# ble-usb-v1_0.net
KiCad netlist of a schematic drawn in EAGLE
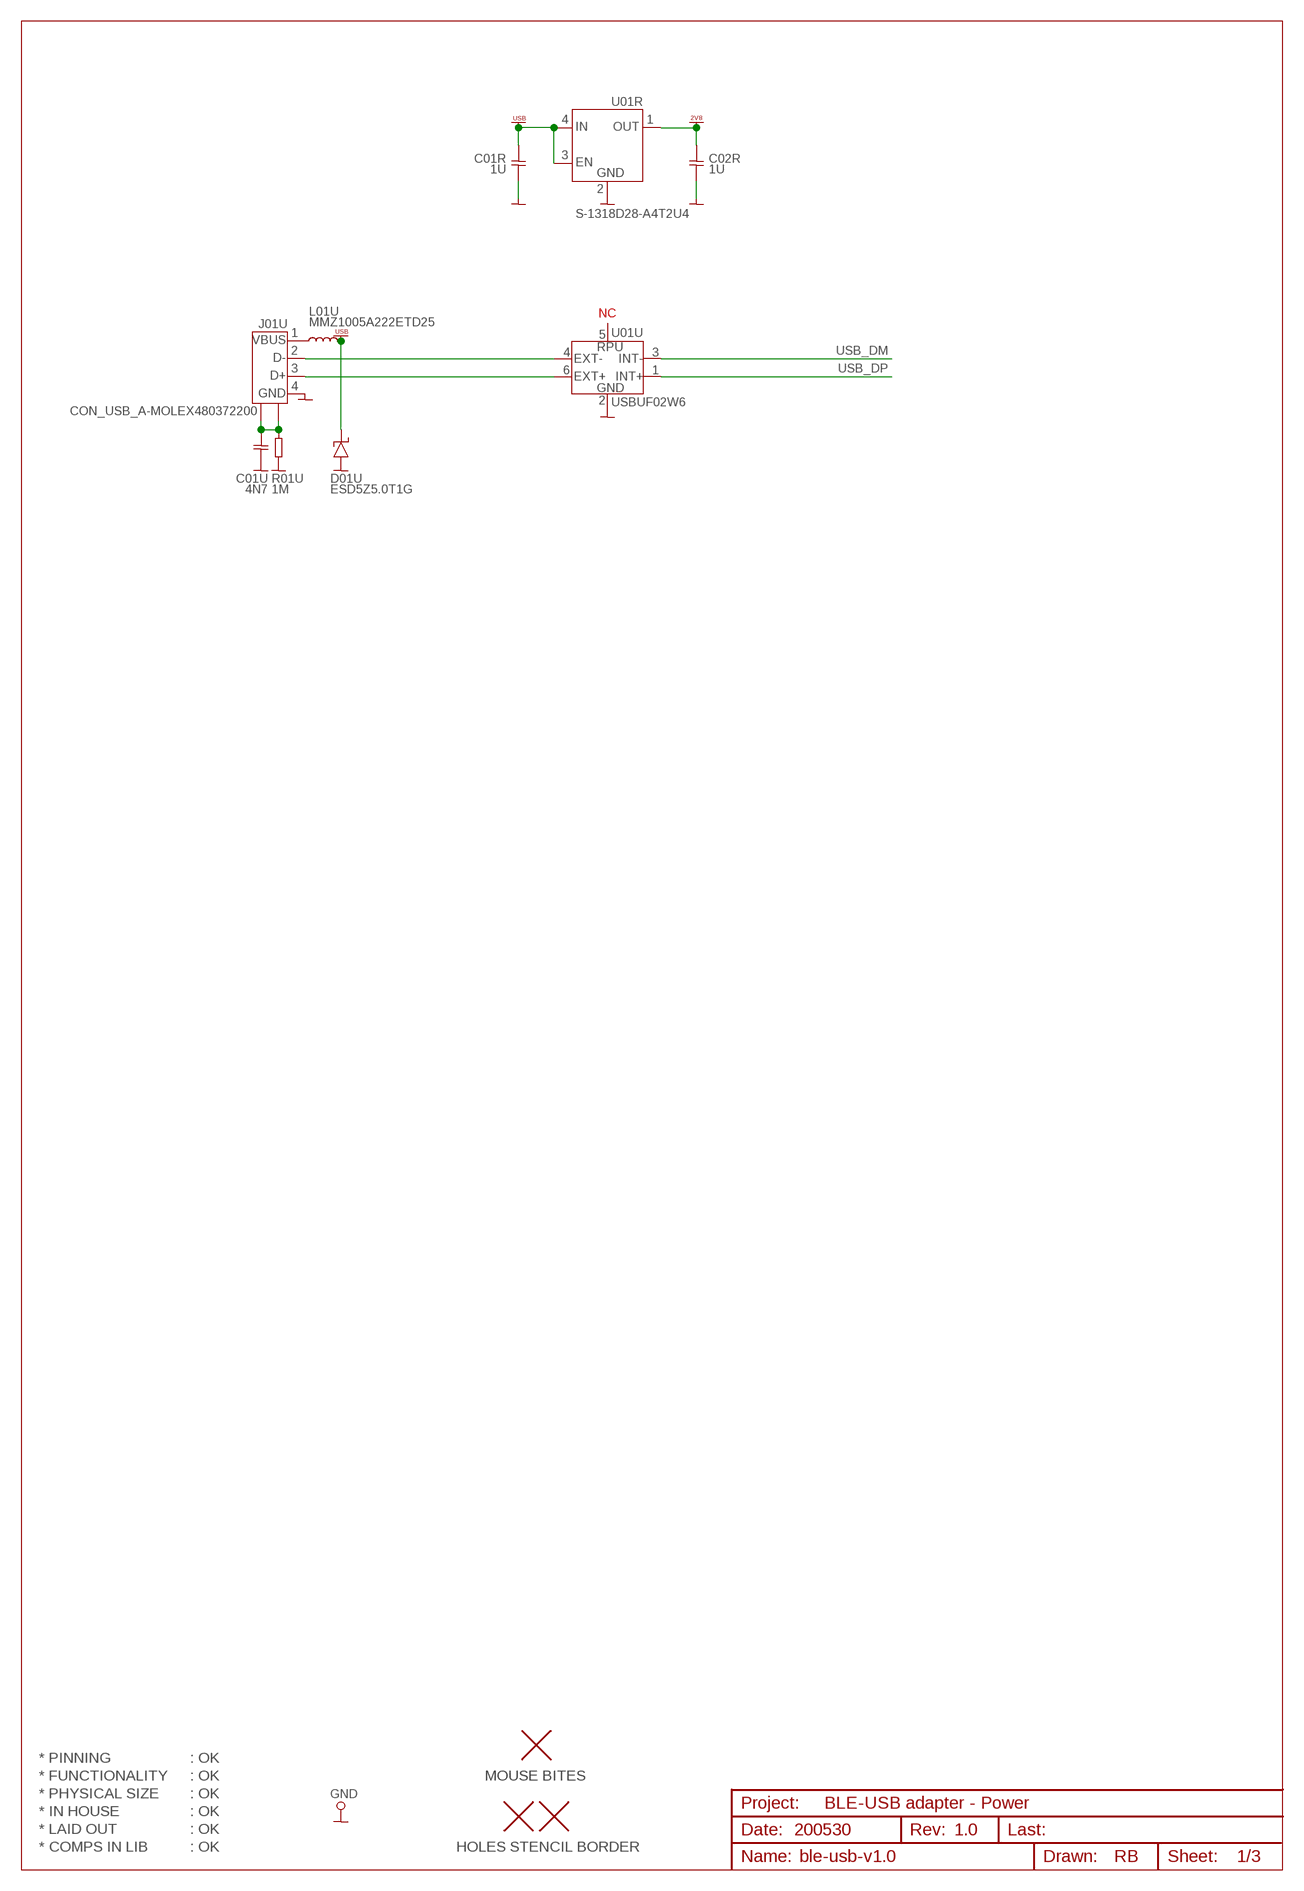
[diagram p0: schematic, sheet 1]
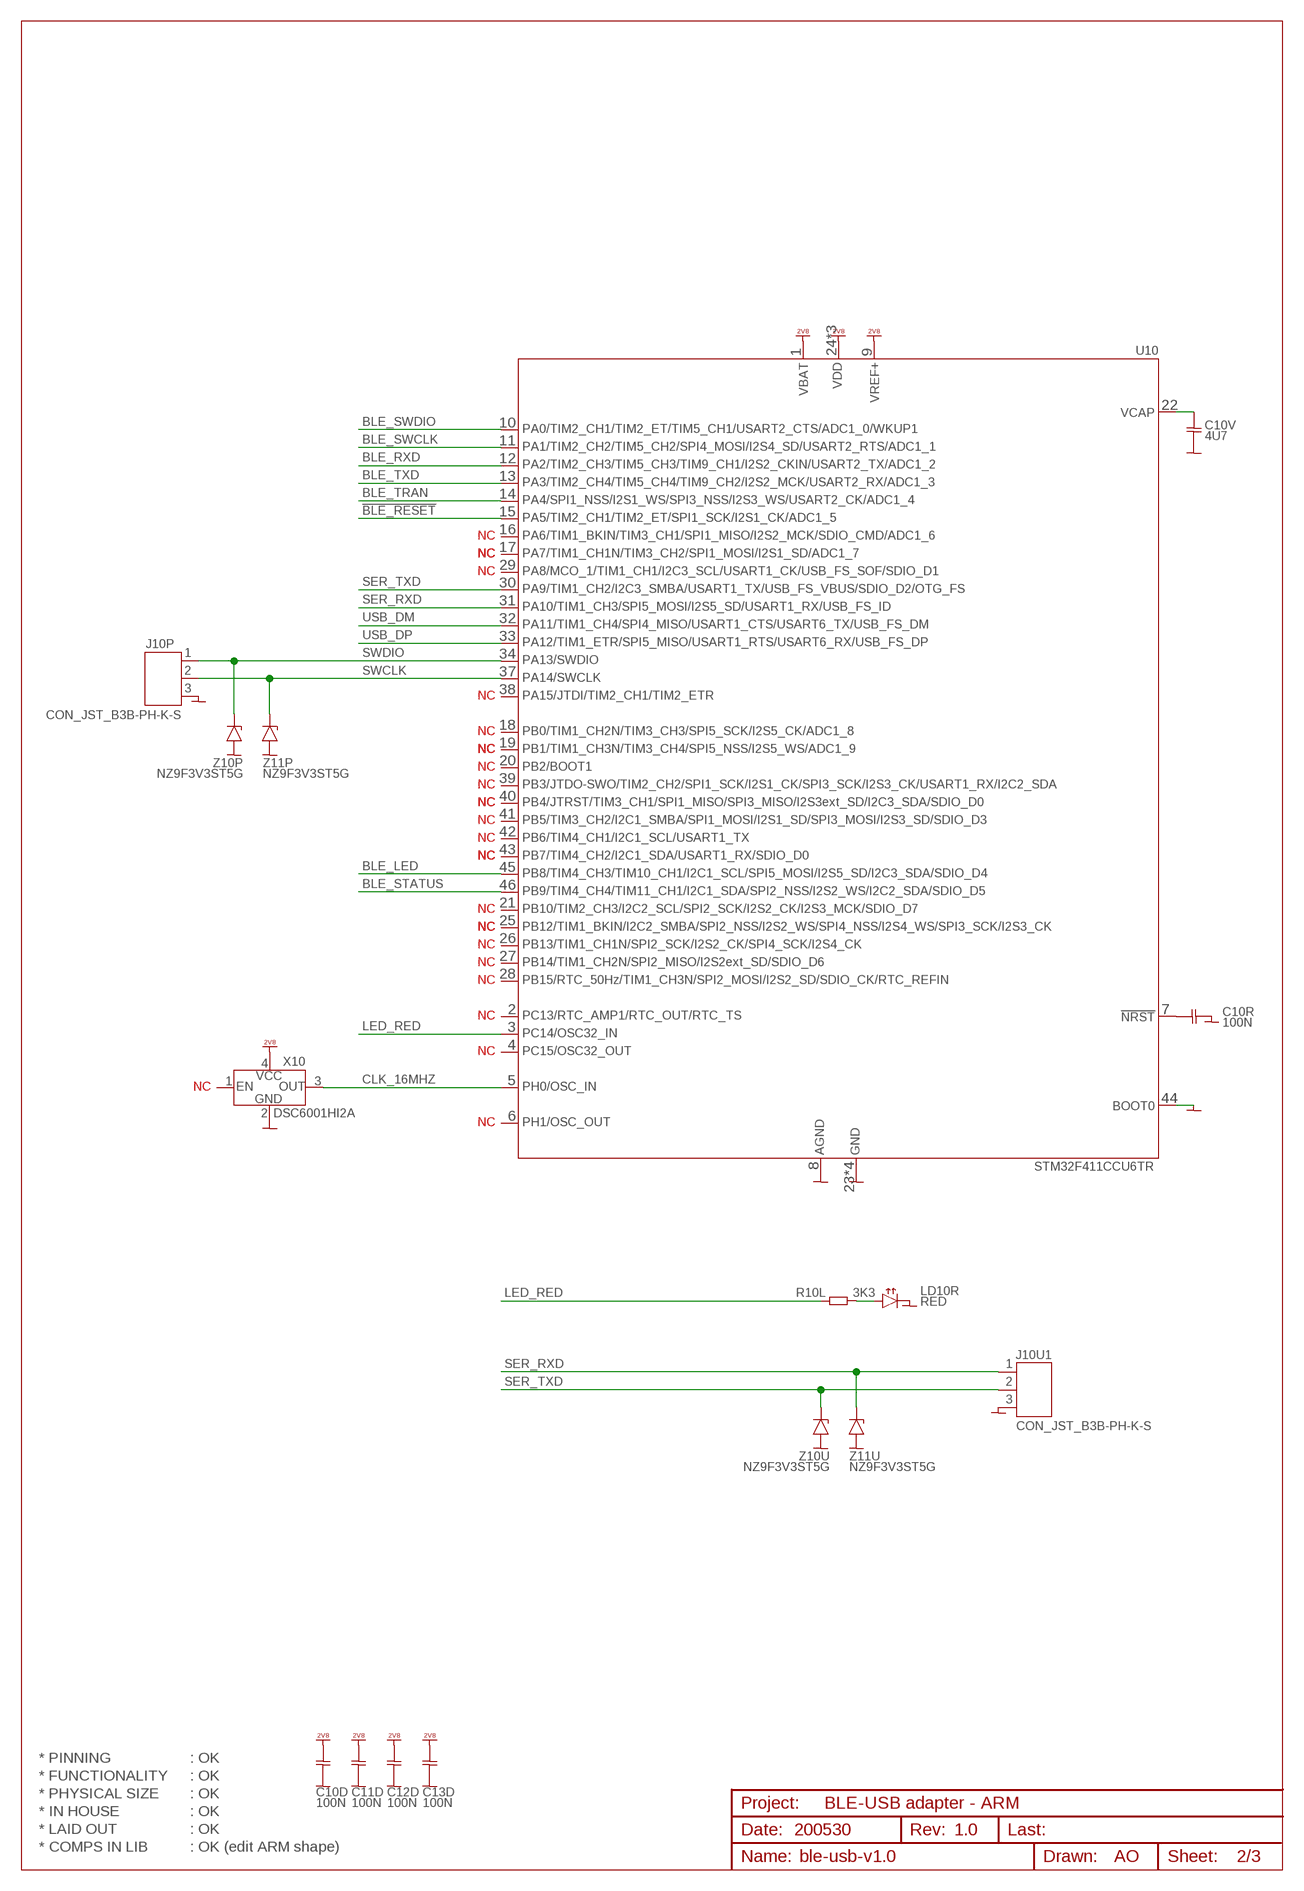
[diagram p1: schematic, sheet 2]
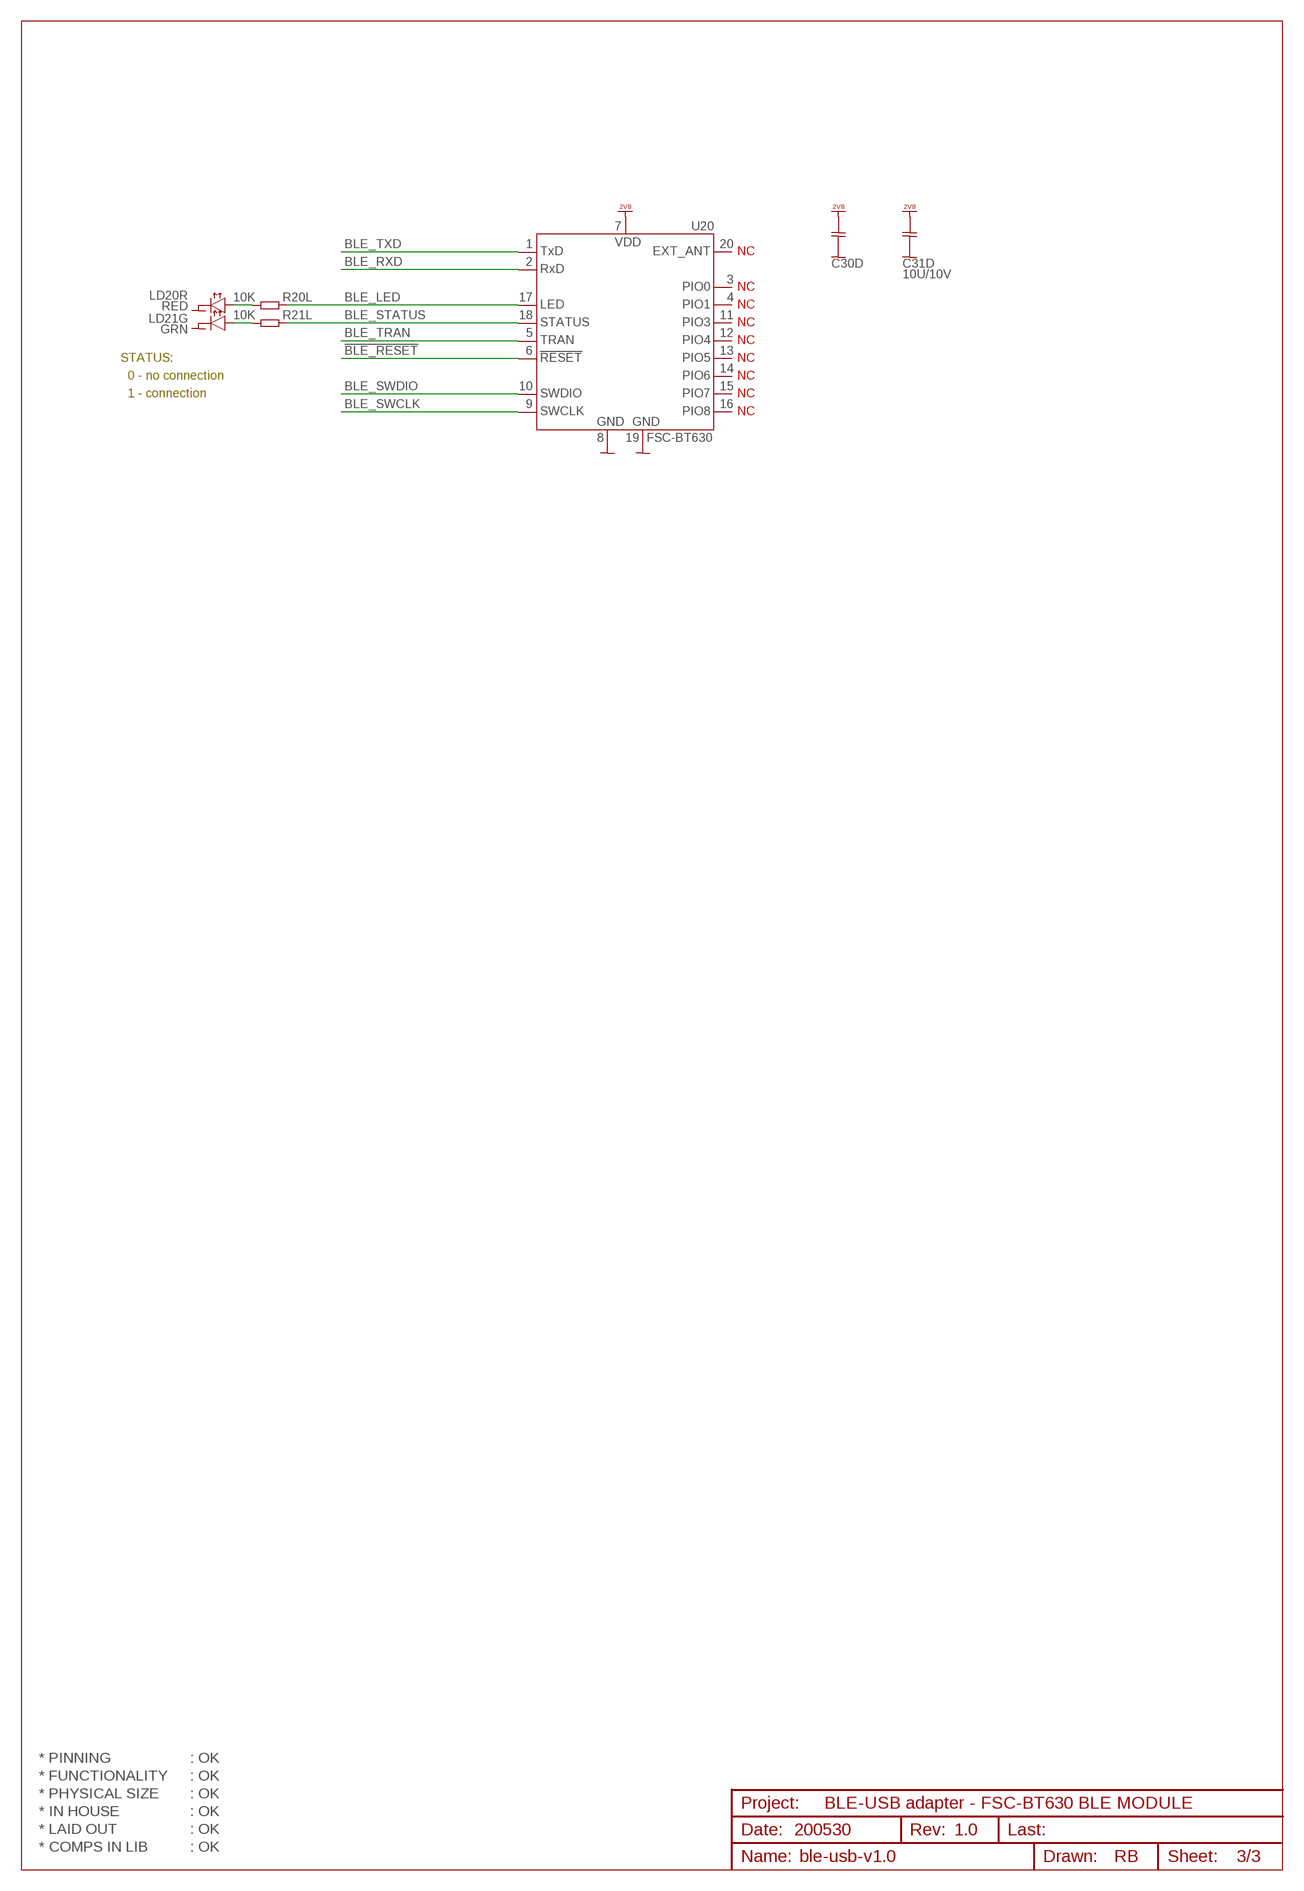
[diagram p2: schematic, sheet 3]

(export (version "E")
  (design (tool "Eeschema 10.0.6"))
  (components
    (comp (ref "C01R")
      (value "1U")
      (footprint "eagle-import:CAP0402")
      (libsource (lib "eagle-import") (part "CAP0402"))
    )
    (comp (ref "C01U")
      (value "4N7")
      (footprint "eagle-import:CAP0402")
      (libsource (lib "eagle-import") (part "CAP0402"))
    )
    (comp (ref "C02R")
      (value "1U")
      (footprint "eagle-import:CAP0402")
      (libsource (lib "eagle-import") (part "CAP0402"))
    )
    (comp (ref "D01U")
      (value "ESD5Z5.0T1G")
      (footprint "eagle-import:DIODE_SOD523")
      (libsource (lib "eagle-import") (part "DIODE_TVS_SOD523"))
    )
    (comp (ref "GND")
      (value "PIN_TEST_0.6MM")
      (footprint "eagle-import:HOLE_PTH_0.6MM")
      (libsource (lib "eagle-import") (part "PIN_TEST_0.6MM"))
    )
    (comp (ref "H1")
      (value "HOLE_NPTH_3.0MM-STENCILBORDER")
      (footprint "eagle-import:HOLE_NPTH_3,0MM-STECILBORDER")
      (libsource (lib "eagle-import") (part "HOLE_NPTH_3.0MM-STENCILBORDER"))
    )
    (comp (ref "H2")
      (value "HOLE_NPTH_3.0MM-STENCILBORDER")
      (footprint "eagle-import:HOLE_NPTH_3,0MM-STECILBORDER")
      (libsource (lib "eagle-import") (part "HOLE_NPTH_3.0MM-STENCILBORDER"))
    )
    (comp (ref "H10")
      (value "HOLE_MOUSEBITES")
      (footprint "eagle-import:HOLE_NPTH_0.5MM")
      (libsource (lib "eagle-import") (part "HOLE_MOUSEBITES"))
    )
    (comp (ref "J01U")
      (value "CON_USB_A-MOLEX480372200")
      (footprint "eagle-import:CON_USB_A-MOLEX480372200")
      (libsource (lib "eagle-import") (part "CON_USB_A-MOLEX480372200"))
    )
    (comp (ref "L01U")
      (value "MMZ1005A222ETD25")
      (footprint "eagle-import:L_0402")
      (libsource (lib "eagle-import") (part "L_0402"))
    )
    (comp (ref "R01U")
      (value "1M")
      (footprint "eagle-import:RES0402")
      (libsource (lib "eagle-import") (part "RES0402"))
    )
    (comp (ref "U01R")
      (value "S-1318D28-A4T2U4")
      (footprint "eagle-import:HSNT-4-B")
      (libsource (lib "eagle-import") (part "S-1318D28-A4T2U4"))
    )
    (comp (ref "U01U")
      (value "USBUF02W6")
      (footprint "eagle-import:SOT323-6L")
      (libsource (lib "eagle-import") (part "USBUF"))
    )
    (comp (ref "C30D")
      (value "100N")
      (footprint "eagle-import:CAP0402")
      (libsource (lib "eagle-import") (part "CAP0402"))
    )
    (comp (ref "C31D")
      (value "10U/10V")
      (footprint "eagle-import:CAP0402")
      (libsource (lib "eagle-import") (part "CAP0402"))
    )
    (comp (ref "LD20R")
      (value "RED")
      (footprint "eagle-import:LED_SMD_0402")
      (libsource (lib "eagle-import") (part "LED_SMD_0402"))
    )
    (comp (ref "LD21G")
      (value "GRN")
      (footprint "eagle-import:LED_SMD_0402")
      (libsource (lib "eagle-import") (part "LED_SMD_0402"))
    )
    (comp (ref "R20L")
      (value "10K")
      (footprint "eagle-import:RES0402")
      (libsource (lib "eagle-import") (part "RES0402"))
    )
    (comp (ref "R21L")
      (value "10K")
      (footprint "eagle-import:RES0402")
      (libsource (lib "eagle-import") (part "RES0402"))
    )
    (comp (ref "U20")
      (value "FSC-BT630")
      (footprint "eagle-import:FSC-BT630")
      (libsource (lib "eagle-import") (part "FSC-BT630"))
    )
    (comp (ref "C10D")
      (value "100N")
      (footprint "eagle-import:CAP0402")
      (libsource (lib "eagle-import") (part "CAP0402"))
    )
    (comp (ref "C10R")
      (value "100N")
      (footprint "eagle-import:CAP0402")
      (libsource (lib "eagle-import") (part "CAP0402"))
    )
    (comp (ref "C10V")
      (value "4U7")
      (footprint "eagle-import:CAP0402")
      (libsource (lib "eagle-import") (part "CAP0402"))
    )
    (comp (ref "C11D")
      (value "100N")
      (footprint "eagle-import:CAP0402")
      (libsource (lib "eagle-import") (part "CAP0402"))
    )
    (comp (ref "C12D")
      (value "100N")
      (footprint "eagle-import:CAP0402")
      (libsource (lib "eagle-import") (part "CAP0402"))
    )
    (comp (ref "C13D")
      (value "100N")
      (footprint "eagle-import:CAP0402")
      (libsource (lib "eagle-import") (part "CAP0402"))
    )
    (comp (ref "J10P")
      (value "CON_JST_B3B-PH-K-S")
      (footprint "eagle-import:CON_JST_B3B-PH-K-S")
      (libsource (lib "eagle-import") (part "CON_JST_B3B-PH-K-S"))
    )
    (comp (ref "J10U1")
      (value "CON_JST_B3B-PH-K-S")
      (footprint "eagle-import:CON_JST_B3B-PH-K-S")
      (libsource (lib "eagle-import") (part "CON_JST_B3B-PH-K-S"))
    )
    (comp (ref "LD10R")
      (value "RED")
      (footprint "eagle-import:LED_SMD_0402")
      (libsource (lib "eagle-import") (part "LED_SMD_0402"))
    )
    (comp (ref "R10L")
      (value "3K3")
      (footprint "eagle-import:RES0402")
      (libsource (lib "eagle-import") (part "RES0402"))
    )
    (comp (ref "U10")
      (value "STM32F411CCU6TR")
      (footprint "eagle-import:VQFN48")
      (libsource (lib "eagle-import") (part "STM32F411CCU6TR"))
    )
    (comp (ref "X10")
      (value "DSC6001HI2A")
      (footprint "eagle-import:VFLGA4_1.6X1.2MM")
      (libsource (lib "eagle-import") (part "DSC6001HI2AVFLGA"))
    )
    (comp (ref "Z10P")
      (value "NZ9F3V3ST5G")
      (footprint "eagle-import:ZENER_SOD923")
      (libsource (lib "eagle-import") (part "ZENER_SOD923"))
    )
    (comp (ref "Z10U")
      (value "NZ9F3V3ST5G")
      (footprint "eagle-import:ZENER_SOD923")
      (libsource (lib "eagle-import") (part "ZENER_SOD923"))
    )
    (comp (ref "Z11P")
      (value "NZ9F3V3ST5G")
      (footprint "eagle-import:ZENER_SOD923")
      (libsource (lib "eagle-import") (part "ZENER_SOD923"))
    )
    (comp (ref "Z11U")
      (value "NZ9F3V3ST5G")
      (footprint "eagle-import:ZENER_SOD923")
      (libsource (lib "eagle-import") (part "ZENER_SOD923"))
    )
  )
  (nets
    (net (code "1") (name "BLE_LED") (class "Default")
      (node (ref "R20L") (pin "1") (pinfunction "1_1") (pintype "passive"))
      (node (ref "U10") (pin "45") (pinfunction "PB8_45") (pintype "passive"))
      (node (ref "U20") (pin "17") (pinfunction "17.LED_17") (pintype "passive"))
    )
    (net (code "2") (name "BLE_RXD") (class "Default")
      (node (ref "U10") (pin "12") (pinfunction "PA2_12") (pintype "passive"))
      (node (ref "U20") (pin "2") (pinfunction "2.RXD_2") (pintype "passive"))
    )
    (net (code "3") (name "BLE_STATUS") (class "Default")
      (node (ref "R21L") (pin "1") (pinfunction "1_1") (pintype "passive"))
      (node (ref "U10") (pin "46") (pinfunction "PB9_46") (pintype "passive"))
      (node (ref "U20") (pin "18") (pinfunction "18.STATUS_18") (pintype "passive"))
    )
    (net (code "4") (name "BLE_SWCLK") (class "Default")
      (node (ref "U10") (pin "11") (pinfunction "PA1_11") (pintype "passive"))
      (node (ref "U20") (pin "9") (pinfunction "9.SWCLK_9") (pintype "passive"))
    )
    (net (code "5") (name "BLE_SWDIO") (class "Default")
      (node (ref "U10") (pin "10") (pinfunction "PA0_10") (pintype "passive"))
      (node (ref "U20") (pin "10") (pinfunction "10.SWDIO_10") (pintype "passive"))
    )
    (net (code "6") (name "BLE_TRAN") (class "Default")
      (node (ref "U10") (pin "14") (pinfunction "PA4_14") (pintype "passive"))
      (node (ref "U20") (pin "5") (pinfunction "5.TRAN_5") (pintype "passive"))
    )
    (net (code "7") (name "BLE_TXD") (class "Default")
      (node (ref "U10") (pin "13") (pinfunction "PA3_13") (pintype "passive"))
      (node (ref "U20") (pin "1") (pinfunction "1.TXD_1") (pintype "passive"))
    )
    (net (code "8") (name "CLK_16MHZ") (class "Default")
      (node (ref "U10") (pin "5") (pinfunction "PH0_5") (pintype "passive"))
      (node (ref "X10") (pin "3") (pinfunction "3.OUT_3") (pintype "passive"))
    )
    (net (code "9") (name "GND") (class "Default")
      (node (ref "C01R") (pin "2") (pinfunction "2_2") (pintype "passive"))
      (node (ref "C01U") (pin "2") (pinfunction "2_2") (pintype "passive"))
      (node (ref "C02R") (pin "2") (pinfunction "2_2") (pintype "passive"))
      (node (ref "C10D") (pin "1") (pinfunction "1_1") (pintype "passive"))
      (node (ref "C10R") (pin "2") (pinfunction "2_2") (pintype "passive"))
      (node (ref "C10V") (pin "2") (pinfunction "2_2") (pintype "passive"))
      (node (ref "C11D") (pin "2") (pinfunction "2_2") (pintype "passive"))
      (node (ref "C12D") (pin "2") (pinfunction "2_2") (pintype "passive"))
      (node (ref "C13D") (pin "2") (pinfunction "2_2") (pintype "passive"))
      (node (ref "C30D") (pin "2") (pinfunction "2_2") (pintype "passive"))
      (node (ref "C31D") (pin "2") (pinfunction "2_2") (pintype "passive"))
      (node (ref "D01U") (pin "A") (pinfunction "A_A") (pintype "passive"))
      (node (ref "GND") (pin "1") (pinfunction "P$1_1") (pintype "passive"))
      (node (ref "J01U") (pin "4") (pinfunction "4.GND_4") (pintype "passive"))
      (node (ref "J10P") (pin "3") (pinfunction "3_3") (pintype "passive"))
      (node (ref "J10U1") (pin "3") (pinfunction "3_3") (pintype "passive"))
      (node (ref "LD10R") (pin "C") (pinfunction "C_C") (pintype "passive"))
      (node (ref "LD20R") (pin "C") (pinfunction "C_C") (pintype "passive"))
      (node (ref "LD21G") (pin "C") (pinfunction "C_C") (pintype "passive"))
      (node (ref "R01U") (pin "2") (pinfunction "2_2") (pintype "passive"))
      (node (ref "U01R") (pin "2") (pinfunction "2.GND_2") (pintype "passive"))
      (node (ref "U01R") (pin "5") (pinfunction "2.GND_5") (pintype "passive"))
      (node (ref "U01U") (pin "2") (pinfunction "2.GND_2") (pintype "passive"))
      (node (ref "U10") (pin "23") (pinfunction "VSS_23") (pintype "passive"))
      (node (ref "U10") (pin "35") (pinfunction "VSS_35") (pintype "passive"))
      (node (ref "U10") (pin "44") (pinfunction "BOOT0_44") (pintype "passive"))
      (node (ref "U10") (pin "47") (pinfunction "VSS_47") (pintype "passive"))
      (node (ref "U10") (pin "8") (pinfunction "VSSA_8") (pintype "passive"))
      (node (ref "U10") (pin "TP") (pinfunction "VSS_TP") (pintype "passive"))
      (node (ref "U20") (pin "19") (pinfunction "19.GND_19") (pintype "passive"))
      (node (ref "U20") (pin "8") (pinfunction "8.GND_8") (pintype "passive"))
      (node (ref "X10") (pin "2") (pinfunction "2.GND_2") (pintype "passive"))
      (node (ref "Z10P") (pin "2") (pinfunction "A_2") (pintype "passive"))
      (node (ref "Z10U") (pin "2") (pinfunction "A_2") (pintype "passive"))
      (node (ref "Z11P") (pin "2") (pinfunction "A_2") (pintype "passive"))
      (node (ref "Z11U") (pin "2") (pinfunction "A_2") (pintype "passive"))
    )
    (net (code "10") (name "LED_RED") (class "Default")
      (node (ref "R10L") (pin "1") (pinfunction "1_1") (pintype "passive"))
      (node (ref "U10") (pin "3") (pinfunction "PC14_3") (pintype "passive"))
    )
    (net (code "11") (name "Net-(J01U-1.VBUS)") (class "Default")
      (node (ref "J01U") (pin "1") (pinfunction "1.VBUS_1") (pintype "passive"))
      (node (ref "L01U") (pin "1") (pinfunction "1_1") (pintype "passive"))
    )
    (net (code "12") (name "Net-(J01U-2.D-)") (class "Default")
      (node (ref "J01U") (pin "2") (pinfunction "2.D-_2") (pintype "passive"))
      (node (ref "U01U") (pin "4") (pinfunction "4.EXT-_4") (pintype "passive"))
    )
    (net (code "13") (name "Net-(J01U-3.D+)") (class "Default")
      (node (ref "J01U") (pin "3") (pinfunction "3.D+_3") (pintype "passive"))
      (node (ref "U01U") (pin "6") (pinfunction "6.EXT+_6") (pintype "passive"))
    )
    (net (code "14") (name "Net-(J01U-5.CASE)") (class "Default")
      (node (ref "C01U") (pin "1") (pinfunction "1_1") (pintype "passive"))
      (node (ref "J01U") (pin "CASE1") (pinfunction "5.CASE_CASE1") (pintype "bidirectional"))
      (node (ref "J01U") (pin "CASE2") (pinfunction "6.CASE_CASE2") (pintype "bidirectional"))
      (node (ref "R01U") (pin "1") (pinfunction "1_1") (pintype "passive"))
    )
    (net (code "15") (name "Net-(LD10R-PadA)") (class "Default")
      (node (ref "LD10R") (pin "A") (pinfunction "A_A") (pintype "passive"))
      (node (ref "R10L") (pin "2") (pinfunction "2_2") (pintype "passive"))
    )
    (net (code "16") (name "Net-(LD20R-PadA)") (class "Default")
      (node (ref "LD20R") (pin "A") (pinfunction "A_A") (pintype "passive"))
      (node (ref "R20L") (pin "2") (pinfunction "2_2") (pintype "passive"))
    )
    (net (code "17") (name "Net-(LD21G-PadA)") (class "Default")
      (node (ref "LD21G") (pin "A") (pinfunction "A_A") (pintype "passive"))
      (node (ref "R21L") (pin "2") (pinfunction "2_2") (pintype "passive"))
    )
    (net (code "18") (name "Net-(U10-NRST)") (class "Default")
      (node (ref "C10R") (pin "1") (pinfunction "1_1") (pintype "passive"))
      (node (ref "U10") (pin "7") (pinfunction "NRST_7") (pintype "passive"))
    )
    (net (code "19") (name "Net-(U10-VCAP)") (class "Default")
      (node (ref "C10V") (pin "1") (pinfunction "1_1") (pintype "passive"))
      (node (ref "U10") (pin "22") (pinfunction "VCAP_22") (pintype "passive"))
    )
    (net (code "20") (name "SER_RXD") (class "Default")
      (node (ref "J10U1") (pin "1") (pinfunction "1_1") (pintype "passive"))
      (node (ref "U10") (pin "31") (pinfunction "PA10_31") (pintype "passive"))
      (node (ref "Z11U") (pin "1") (pinfunction "C_1") (pintype "passive"))
    )
    (net (code "21") (name "SER_TXD") (class "Default")
      (node (ref "J10U1") (pin "2") (pinfunction "2_2") (pintype "passive"))
      (node (ref "U10") (pin "30") (pinfunction "PA9_30") (pintype "passive"))
      (node (ref "Z10U") (pin "1") (pinfunction "C_1") (pintype "passive"))
    )
    (net (code "22") (name "SWCLK") (class "Default")
      (node (ref "J10P") (pin "2") (pinfunction "2_2") (pintype "passive"))
      (node (ref "U10") (pin "37") (pinfunction "PA14_37") (pintype "passive"))
      (node (ref "Z11P") (pin "1") (pinfunction "C_1") (pintype "passive"))
    )
    (net (code "23") (name "SWDIO") (class "Default")
      (node (ref "J10P") (pin "1") (pinfunction "1_1") (pintype "passive"))
      (node (ref "U10") (pin "34") (pinfunction "PA13_34") (pintype "passive"))
      (node (ref "Z10P") (pin "1") (pinfunction "C_1") (pintype "passive"))
    )
    (net (code "24") (name "USB_DM") (class "Default")
      (node (ref "U01U") (pin "3") (pinfunction "3.INT-_3") (pintype "passive"))
      (node (ref "U10") (pin "32") (pinfunction "PA11_32") (pintype "passive"))
    )
    (net (code "25") (name "USB_DP") (class "Default")
      (node (ref "U01U") (pin "1") (pinfunction "1.INT+_1") (pintype "passive"))
      (node (ref "U10") (pin "33") (pinfunction "PA12_33") (pintype "passive"))
    )
    (net (code "26") (name "VDD_2V8") (class "Default")
      (node (ref "C02R") (pin "1") (pinfunction "1_1") (pintype "passive"))
      (node (ref "C10D") (pin "2") (pinfunction "2_2") (pintype "passive"))
      (node (ref "C11D") (pin "1") (pinfunction "1_1") (pintype "passive"))
      (node (ref "C12D") (pin "1") (pinfunction "1_1") (pintype "passive"))
      (node (ref "C13D") (pin "1") (pinfunction "1_1") (pintype "passive"))
      (node (ref "C30D") (pin "1") (pinfunction "1_1") (pintype "passive"))
      (node (ref "C31D") (pin "1") (pinfunction "1_1") (pintype "passive"))
      (node (ref "U01R") (pin "1") (pinfunction "1.OUT_1") (pintype "passive"))
      (node (ref "U10") (pin "1") (pinfunction "VBAT_1") (pintype "passive"))
      (node (ref "U10") (pin "24") (pinfunction "VDD_24") (pintype "passive"))
      (node (ref "U10") (pin "36") (pinfunction "VDD_36") (pintype "passive"))
      (node (ref "U10") (pin "48") (pinfunction "VDD_48") (pintype "passive"))
      (node (ref "U10") (pin "9") (pinfunction "VREF+_9") (pintype "passive"))
      (node (ref "U20") (pin "7") (pinfunction "7.VDD_7") (pintype "passive"))
      (node (ref "X10") (pin "4") (pinfunction "4.VCC_4") (pintype "passive"))
    )
    (net (code "27") (name "VDD_USB") (class "Default")
      (node (ref "C01R") (pin "1") (pinfunction "1_1") (pintype "passive"))
      (node (ref "D01U") (pin "C") (pinfunction "C_C") (pintype "passive"))
      (node (ref "L01U") (pin "2") (pinfunction "2_2") (pintype "passive"))
      (node (ref "U01R") (pin "3") (pinfunction "3.EN_3") (pintype "passive"))
      (node (ref "U01R") (pin "4") (pinfunction "4.IN_4") (pintype "passive"))
    )
    (net (code "28") (name "unconnected-(U01U-5.RPU-Pad5)") (class "Default")
      (node (ref "U01U") (pin "5") (pinfunction "5.RPU_5") (pintype "passive"))
    )
    (net (code "29") (name "unconnected-(U10-PA6-Pad16)") (class "Default")
      (node (ref "U10") (pin "16") (pinfunction "PA6_16") (pintype "passive"))
    )
    (net (code "30") (name "unconnected-(U10-PA7-Pad17)") (class "Default")
      (node (ref "U10") (pin "17") (pinfunction "PA7_17") (pintype "passive"))
    )
    (net (code "31") (name "unconnected-(U10-PA8-Pad29)") (class "Default")
      (node (ref "U10") (pin "29") (pinfunction "PA8_29") (pintype "passive"))
    )
    (net (code "32") (name "unconnected-(U10-PA15-Pad38)") (class "Default")
      (node (ref "U10") (pin "38") (pinfunction "PA15_38") (pintype "passive"))
    )
    (net (code "33") (name "unconnected-(U10-PB0-Pad18)") (class "Default")
      (node (ref "U10") (pin "18") (pinfunction "PB0_18") (pintype "passive"))
    )
    (net (code "34") (name "unconnected-(U10-PB1-Pad19)") (class "Default")
      (node (ref "U10") (pin "19") (pinfunction "PB1_19") (pintype "passive"))
    )
    (net (code "35") (name "unconnected-(U10-PB2-Pad20)") (class "Default")
      (node (ref "U10") (pin "20") (pinfunction "PB2_20") (pintype "passive"))
    )
    (net (code "36") (name "unconnected-(U10-PB3-Pad39)") (class "Default")
      (node (ref "U10") (pin "39") (pinfunction "PB3_39") (pintype "passive"))
    )
    (net (code "37") (name "unconnected-(U10-PB4-Pad40)") (class "Default")
      (node (ref "U10") (pin "40") (pinfunction "PB4_40") (pintype "passive"))
    )
    (net (code "38") (name "unconnected-(U10-PB5-Pad41)") (class "Default")
      (node (ref "U10") (pin "41") (pinfunction "PB5_41") (pintype "passive"))
    )
    (net (code "39") (name "unconnected-(U10-PB6-Pad42)") (class "Default")
      (node (ref "U10") (pin "42") (pinfunction "PB6_42") (pintype "passive"))
    )
    (net (code "40") (name "unconnected-(U10-PB7-Pad43)") (class "Default")
      (node (ref "U10") (pin "43") (pinfunction "PB7_43") (pintype "passive"))
    )
    (net (code "41") (name "unconnected-(U10-PB10-Pad21)") (class "Default")
      (node (ref "U10") (pin "21") (pinfunction "PB10_21") (pintype "passive"))
    )
    (net (code "42") (name "unconnected-(U10-PB12-Pad25)") (class "Default")
      (node (ref "U10") (pin "25") (pinfunction "PB12_25") (pintype "passive"))
    )
    (net (code "43") (name "unconnected-(U10-PB13-Pad26)") (class "Default")
      (node (ref "U10") (pin "26") (pinfunction "PB13_26") (pintype "passive"))
    )
    (net (code "44") (name "unconnected-(U10-PB14-Pad27)") (class "Default")
      (node (ref "U10") (pin "27") (pinfunction "PB14_27") (pintype "passive"))
    )
    (net (code "45") (name "unconnected-(U10-PB15-Pad28)") (class "Default")
      (node (ref "U10") (pin "28") (pinfunction "PB15_28") (pintype "passive"))
    )
    (net (code "46") (name "unconnected-(U10-PC13-Pad2)") (class "Default")
      (node (ref "U10") (pin "2") (pinfunction "PC13_2") (pintype "passive"))
    )
    (net (code "47") (name "unconnected-(U10-PC15-Pad4)") (class "Default")
      (node (ref "U10") (pin "4") (pinfunction "PC15_4") (pintype "passive"))
    )
    (net (code "48") (name "unconnected-(U10-PH1-Pad6)") (class "Default")
      (node (ref "U10") (pin "6") (pinfunction "PH1_6") (pintype "passive"))
    )
    (net (code "49") (name "unconnected-(U20-3.PIO0-Pad3)") (class "Default")
      (node (ref "U20") (pin "3") (pinfunction "3.PIO0_3") (pintype "passive"))
    )
    (net (code "50") (name "unconnected-(U20-4.PIO1-Pad4)") (class "Default")
      (node (ref "U20") (pin "4") (pinfunction "4.PIO1_4") (pintype "passive"))
    )
    (net (code "51") (name "unconnected-(U20-11.PIO3-Pad11)") (class "Default")
      (node (ref "U20") (pin "11") (pinfunction "11.PIO3_11") (pintype "passive"))
    )
    (net (code "52") (name "unconnected-(U20-12.PIO4-Pad12)") (class "Default")
      (node (ref "U20") (pin "12") (pinfunction "12.PIO4_12") (pintype "passive"))
    )
    (net (code "53") (name "unconnected-(U20-13.PIO5-Pad13)") (class "Default")
      (node (ref "U20") (pin "13") (pinfunction "13.PIO5_13") (pintype "passive"))
    )
    (net (code "54") (name "unconnected-(U20-14.PIO6-Pad14)") (class "Default")
      (node (ref "U20") (pin "14") (pinfunction "14.PIO6_14") (pintype "passive"))
    )
    (net (code "55") (name "unconnected-(U20-15.PIO7-Pad15)") (class "Default")
      (node (ref "U20") (pin "15") (pinfunction "15.PIO7_15") (pintype "passive"))
    )
    (net (code "56") (name "unconnected-(U20-16.PIO8-Pad16)") (class "Default")
      (node (ref "U20") (pin "16") (pinfunction "16.PIO8_16") (pintype "passive"))
    )
    (net (code "57") (name "unconnected-(U20-20.EXT_ANT-Pad20)") (class "Default")
      (node (ref "U20") (pin "20") (pinfunction "20.EXT_ANT_20") (pintype "passive"))
    )
    (net (code "58") (name "unconnected-(X10-1.EN-Pad1)") (class "Default")
      (node (ref "X10") (pin "1") (pinfunction "1.EN_1") (pintype "passive"))
    )
    (net (code "59") (name "~{BLE_RESET}") (class "Default")
      (node (ref "U10") (pin "15") (pinfunction "PA5_15") (pintype "passive"))
      (node (ref "U20") (pin "6") (pinfunction "6.~{RESET}_6") (pintype "passive"))
    )
  )
)
